# DashDial.net
KiCad netlist of a schematic drawn in EAGLE
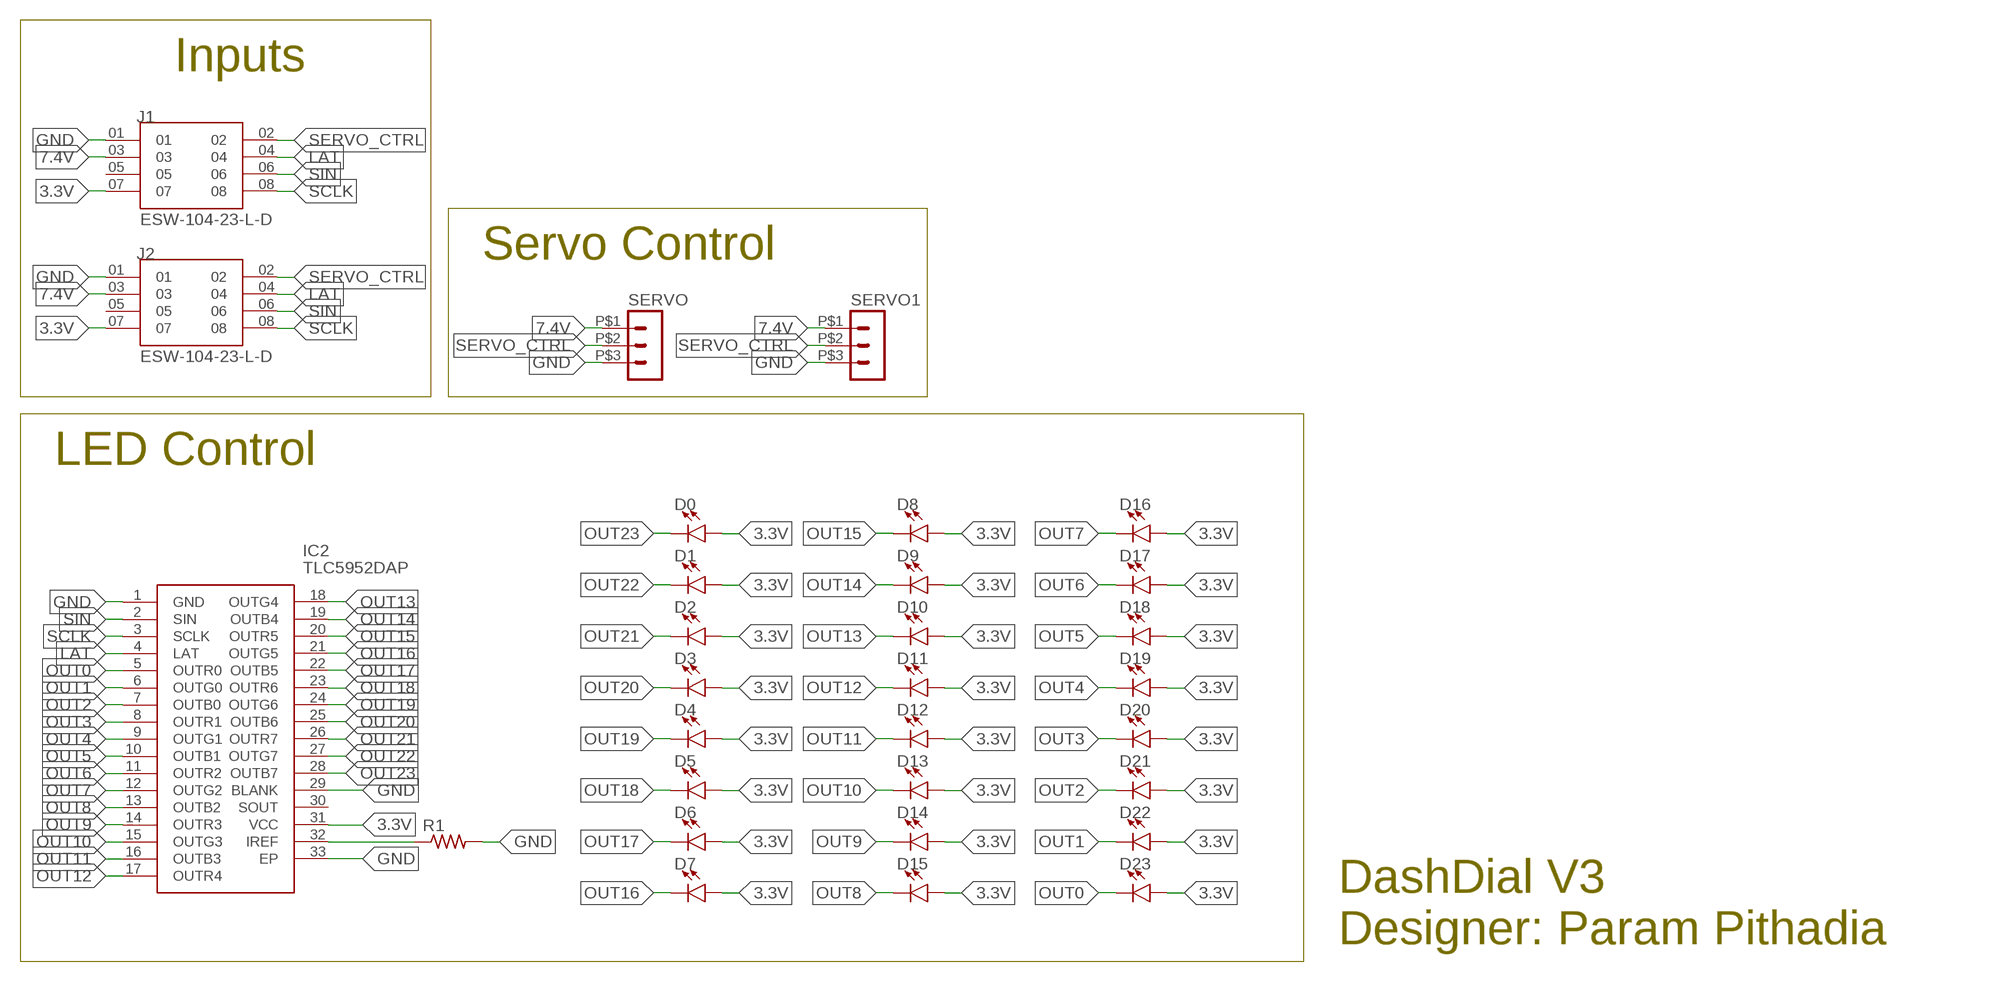
[diagram p0: schematic, sheet 1]

(export (version "E")
  (design (tool "Eeschema 10.0.6"))
  (components
    (comp (ref "D0")
      (value "LED3MM")
      (footprint "eagle-import:LED_3MM")
      (libsource (lib "eagle-import") (part "LED3MM"))
    )
    (comp (ref "D1")
      (value "LED3MM")
      (footprint "eagle-import:LED_3MM")
      (libsource (lib "eagle-import") (part "LED3MM"))
    )
    (comp (ref "D2")
      (value "LED3MM")
      (footprint "eagle-import:LED_3MM")
      (libsource (lib "eagle-import") (part "LED3MM"))
    )
    (comp (ref "D3")
      (value "LED3MM")
      (footprint "eagle-import:LED_3MM")
      (libsource (lib "eagle-import") (part "LED3MM"))
    )
    (comp (ref "D4")
      (value "LED3MM")
      (footprint "eagle-import:LED_3MM")
      (libsource (lib "eagle-import") (part "LED3MM"))
    )
    (comp (ref "D5")
      (value "LED3MM")
      (footprint "eagle-import:LED_3MM")
      (libsource (lib "eagle-import") (part "LED3MM"))
    )
    (comp (ref "D6")
      (value "LED3MM")
      (footprint "eagle-import:LED_3MM")
      (libsource (lib "eagle-import") (part "LED3MM"))
    )
    (comp (ref "D7")
      (value "LED3MM")
      (footprint "eagle-import:LED_3MM")
      (libsource (lib "eagle-import") (part "LED3MM"))
    )
    (comp (ref "D8")
      (value "LED3MM")
      (footprint "eagle-import:LED_3MM")
      (libsource (lib "eagle-import") (part "LED3MM"))
    )
    (comp (ref "D9")
      (value "LED3MM")
      (footprint "eagle-import:LED_3MM")
      (libsource (lib "eagle-import") (part "LED3MM"))
    )
    (comp (ref "D10")
      (value "LED3MM")
      (footprint "eagle-import:LED_3MM")
      (libsource (lib "eagle-import") (part "LED3MM"))
    )
    (comp (ref "D11")
      (value "LED3MM")
      (footprint "eagle-import:LED_3MM")
      (libsource (lib "eagle-import") (part "LED3MM"))
    )
    (comp (ref "D12")
      (value "LED3MM")
      (footprint "eagle-import:LED_3MM")
      (libsource (lib "eagle-import") (part "LED3MM"))
    )
    (comp (ref "D13")
      (value "LED3MM")
      (footprint "eagle-import:LED_3MM")
      (libsource (lib "eagle-import") (part "LED3MM"))
    )
    (comp (ref "D14")
      (value "LED3MM")
      (footprint "eagle-import:LED_3MM")
      (libsource (lib "eagle-import") (part "LED3MM"))
    )
    (comp (ref "D15")
      (value "LED3MM")
      (footprint "eagle-import:LED_3MM")
      (libsource (lib "eagle-import") (part "LED3MM"))
    )
    (comp (ref "D16")
      (value "LED3MM")
      (footprint "eagle-import:LED_3MM")
      (libsource (lib "eagle-import") (part "LED3MM"))
    )
    (comp (ref "D17")
      (value "LED3MM")
      (footprint "eagle-import:LED_3MM")
      (libsource (lib "eagle-import") (part "LED3MM"))
    )
    (comp (ref "D18")
      (value "LED3MM")
      (footprint "eagle-import:LED_3MM")
      (libsource (lib "eagle-import") (part "LED3MM"))
    )
    (comp (ref "D19")
      (value "LED3MM")
      (footprint "eagle-import:LED_3MM")
      (libsource (lib "eagle-import") (part "LED3MM"))
    )
    (comp (ref "D20")
      (value "LED3MM")
      (footprint "eagle-import:LED_3MM")
      (libsource (lib "eagle-import") (part "LED3MM"))
    )
    (comp (ref "D21")
      (value "LED3MM")
      (footprint "eagle-import:LED_3MM")
      (libsource (lib "eagle-import") (part "LED3MM"))
    )
    (comp (ref "D22")
      (value "LED3MM")
      (footprint "eagle-import:LED_3MM")
      (libsource (lib "eagle-import") (part "LED3MM"))
    )
    (comp (ref "D23")
      (value "LED3MM")
      (footprint "eagle-import:LED_3MM")
      (libsource (lib "eagle-import") (part "LED3MM"))
    )
    (comp (ref "IC2")
      (value "TLC5952DAP")
      (footprint "eagle-import:SOP65P810X120-33N")
      (fields (field (name "MOUSER_PART_NUMBER") "595-TLC5952DAP"))
      (libsource (lib "eagle-import") (part "TLC5952DAP"))
    )
    (comp (ref "J1")
      (value "ESW-104-23-L-D")
      (footprint "eagle-import:SAMTEC_ESW-104-23-L-D")
      (fields (field (name "MANUFACTURER") "Samtec Inc."))
      (libsource (lib "eagle-import") (part "ESW-104-23-L-D"))
    )
    (comp (ref "J2")
      (value "ESW-104-23-L-D")
      (footprint "eagle-import:SAMTEC_ESW-104-23-L-D")
      (fields (field (name "MANUFACTURER") "Samtec Inc."))
      (libsource (lib "eagle-import") (part "ESW-104-23-L-D"))
    )
    (comp (ref "R1")
      (value "RES_SMDR0603")
      (footprint "eagle-import:R0603")
      (libsource (lib "eagle-import") (part "RES_SMDR0603"))
    )
    (comp (ref "SERVO")
      (value "HEADER_POS3_43650-0300")
      (footprint "eagle-import:43650-0300")
      (libsource (lib "eagle-import") (part "HEADER_POS3_?43650-0300"))
    )
    (comp (ref "SERVO1")
      (value "HEADER_POS3_43650-0300")
      (footprint "eagle-import:43650-0300")
      (libsource (lib "eagle-import") (part "HEADER_POS3_?43650-0300"))
    )
  )
  (nets
    (net (code "1") (name "3.3V") (class "Default")
      (node (ref "D0") (pin "A") (pinfunction "A_A") (pintype "passive"))
      (node (ref "D1") (pin "A") (pinfunction "A_A") (pintype "passive"))
      (node (ref "D10") (pin "A") (pinfunction "A_A") (pintype "passive"))
      (node (ref "D11") (pin "A") (pinfunction "A_A") (pintype "passive"))
      (node (ref "D12") (pin "A") (pinfunction "A_A") (pintype "passive"))
      (node (ref "D13") (pin "A") (pinfunction "A_A") (pintype "passive"))
      (node (ref "D14") (pin "A") (pinfunction "A_A") (pintype "passive"))
      (node (ref "D15") (pin "A") (pinfunction "A_A") (pintype "passive"))
      (node (ref "D16") (pin "A") (pinfunction "A_A") (pintype "passive"))
      (node (ref "D17") (pin "A") (pinfunction "A_A") (pintype "passive"))
      (node (ref "D18") (pin "A") (pinfunction "A_A") (pintype "passive"))
      (node (ref "D19") (pin "A") (pinfunction "A_A") (pintype "passive"))
      (node (ref "D2") (pin "A") (pinfunction "A_A") (pintype "passive"))
      (node (ref "D20") (pin "A") (pinfunction "A_A") (pintype "passive"))
      (node (ref "D21") (pin "A") (pinfunction "A_A") (pintype "passive"))
      (node (ref "D22") (pin "A") (pinfunction "A_A") (pintype "passive"))
      (node (ref "D23") (pin "A") (pinfunction "A_A") (pintype "passive"))
      (node (ref "D3") (pin "A") (pinfunction "A_A") (pintype "passive"))
      (node (ref "D4") (pin "A") (pinfunction "A_A") (pintype "passive"))
      (node (ref "D5") (pin "A") (pinfunction "A_A") (pintype "passive"))
      (node (ref "D6") (pin "A") (pinfunction "A_A") (pintype "passive"))
      (node (ref "D7") (pin "A") (pinfunction "A_A") (pintype "passive"))
      (node (ref "D8") (pin "A") (pinfunction "A_A") (pintype "passive"))
      (node (ref "D9") (pin "A") (pinfunction "A_A") (pintype "passive"))
      (node (ref "IC2") (pin "31") (pinfunction "VCC_31") (pintype "bidirectional"))
      (node (ref "J1") (pin "07") (pinfunction "07_07") (pintype "passive"))
      (node (ref "J2") (pin "07") (pinfunction "07_07") (pintype "passive"))
    )
    (net (code "2") (name "7.4V") (class "Default")
      (node (ref "J1") (pin "03") (pinfunction "03_03") (pintype "passive"))
      (node (ref "J2") (pin "03") (pinfunction "03_03") (pintype "passive"))
      (node (ref "SERVO") (pin "P$1") (pinfunction "1_P$1") (pintype "passive"))
      (node (ref "SERVO1") (pin "P$1") (pinfunction "1_P$1") (pintype "passive"))
    )
    (net (code "3") (name "GND") (class "Default")
      (node (ref "IC2") (pin "1") (pinfunction "GND_1") (pintype "bidirectional"))
      (node (ref "IC2") (pin "29") (pinfunction "BLANK_29") (pintype "bidirectional"))
      (node (ref "IC2") (pin "33") (pinfunction "EP_33") (pintype "bidirectional"))
      (node (ref "J1") (pin "01") (pinfunction "01_01") (pintype "passive"))
      (node (ref "J2") (pin "01") (pinfunction "01_01") (pintype "passive"))
      (node (ref "R1") (pin "2") (pinfunction "2_2") (pintype "passive"))
      (node (ref "SERVO") (pin "P$3") (pinfunction "3_P$3") (pintype "passive"))
      (node (ref "SERVO1") (pin "P$3") (pinfunction "3_P$3") (pintype "passive"))
    )
    (net (code "4") (name "LAT") (class "Default")
      (node (ref "IC2") (pin "4") (pinfunction "LAT_4") (pintype "bidirectional"))
      (node (ref "J1") (pin "04") (pinfunction "04_04") (pintype "passive"))
      (node (ref "J2") (pin "04") (pinfunction "04_04") (pintype "passive"))
    )
    (net (code "5") (name "Net-(IC2-IREF)") (class "Default")
      (node (ref "IC2") (pin "32") (pinfunction "IREF_32") (pintype "bidirectional"))
      (node (ref "R1") (pin "1") (pinfunction "1_1") (pintype "passive"))
    )
    (net (code "6") (name "OUT0") (class "Default")
      (node (ref "D23") (pin "K") (pinfunction "C_K") (pintype "passive"))
      (node (ref "IC2") (pin "5") (pinfunction "OUTR0_5") (pintype "bidirectional"))
    )
    (net (code "7") (name "OUT1") (class "Default")
      (node (ref "D22") (pin "K") (pinfunction "C_K") (pintype "passive"))
      (node (ref "IC2") (pin "6") (pinfunction "OUTG0_6") (pintype "bidirectional"))
    )
    (net (code "8") (name "OUT2") (class "Default")
      (node (ref "D21") (pin "K") (pinfunction "C_K") (pintype "passive"))
      (node (ref "IC2") (pin "7") (pinfunction "OUTB0_7") (pintype "bidirectional"))
    )
    (net (code "9") (name "OUT3") (class "Default")
      (node (ref "D20") (pin "K") (pinfunction "C_K") (pintype "passive"))
      (node (ref "IC2") (pin "8") (pinfunction "OUTR1_8") (pintype "bidirectional"))
    )
    (net (code "10") (name "OUT4") (class "Default")
      (node (ref "D19") (pin "K") (pinfunction "C_K") (pintype "passive"))
      (node (ref "IC2") (pin "9") (pinfunction "OUTG1_9") (pintype "bidirectional"))
    )
    (net (code "11") (name "OUT5") (class "Default")
      (node (ref "D18") (pin "K") (pinfunction "C_K") (pintype "passive"))
      (node (ref "IC2") (pin "10") (pinfunction "OUTB1_10") (pintype "bidirectional"))
    )
    (net (code "12") (name "OUT6") (class "Default")
      (node (ref "D17") (pin "K") (pinfunction "C_K") (pintype "passive"))
      (node (ref "IC2") (pin "11") (pinfunction "OUTR2_11") (pintype "bidirectional"))
    )
    (net (code "13") (name "OUT7") (class "Default")
      (node (ref "D16") (pin "K") (pinfunction "C_K") (pintype "passive"))
      (node (ref "IC2") (pin "12") (pinfunction "OUTG2_12") (pintype "bidirectional"))
    )
    (net (code "14") (name "OUT8") (class "Default")
      (node (ref "D15") (pin "K") (pinfunction "C_K") (pintype "passive"))
      (node (ref "IC2") (pin "13") (pinfunction "OUTB2_13") (pintype "bidirectional"))
    )
    (net (code "15") (name "OUT9") (class "Default")
      (node (ref "D14") (pin "K") (pinfunction "C_K") (pintype "passive"))
      (node (ref "IC2") (pin "14") (pinfunction "OUTR3_14") (pintype "bidirectional"))
    )
    (net (code "16") (name "OUT10") (class "Default")
      (node (ref "D13") (pin "K") (pinfunction "C_K") (pintype "passive"))
      (node (ref "IC2") (pin "15") (pinfunction "OUTG3_15") (pintype "bidirectional"))
    )
    (net (code "17") (name "OUT11") (class "Default")
      (node (ref "D12") (pin "K") (pinfunction "C_K") (pintype "passive"))
      (node (ref "IC2") (pin "16") (pinfunction "OUTB3_16") (pintype "bidirectional"))
    )
    (net (code "18") (name "OUT12") (class "Default")
      (node (ref "D11") (pin "K") (pinfunction "C_K") (pintype "passive"))
      (node (ref "IC2") (pin "17") (pinfunction "OUTR4_17") (pintype "bidirectional"))
    )
    (net (code "19") (name "OUT13") (class "Default")
      (node (ref "D10") (pin "K") (pinfunction "C_K") (pintype "passive"))
      (node (ref "IC2") (pin "18") (pinfunction "OUTG4_18") (pintype "bidirectional"))
    )
    (net (code "20") (name "OUT14") (class "Default")
      (node (ref "D9") (pin "K") (pinfunction "C_K") (pintype "passive"))
      (node (ref "IC2") (pin "19") (pinfunction "OUTB4_19") (pintype "bidirectional"))
    )
    (net (code "21") (name "OUT15") (class "Default")
      (node (ref "D8") (pin "K") (pinfunction "C_K") (pintype "passive"))
      (node (ref "IC2") (pin "20") (pinfunction "OUTR5_20") (pintype "bidirectional"))
    )
    (net (code "22") (name "OUT16") (class "Default")
      (node (ref "D7") (pin "K") (pinfunction "C_K") (pintype "passive"))
      (node (ref "IC2") (pin "21") (pinfunction "OUTG5_21") (pintype "bidirectional"))
    )
    (net (code "23") (name "OUT17") (class "Default")
      (node (ref "D6") (pin "K") (pinfunction "C_K") (pintype "passive"))
      (node (ref "IC2") (pin "22") (pinfunction "OUTB5_22") (pintype "bidirectional"))
    )
    (net (code "24") (name "OUT18") (class "Default")
      (node (ref "D5") (pin "K") (pinfunction "C_K") (pintype "passive"))
      (node (ref "IC2") (pin "23") (pinfunction "OUTR6_23") (pintype "bidirectional"))
    )
    (net (code "25") (name "OUT19") (class "Default")
      (node (ref "D4") (pin "K") (pinfunction "C_K") (pintype "passive"))
      (node (ref "IC2") (pin "24") (pinfunction "OUTG6_24") (pintype "bidirectional"))
    )
    (net (code "26") (name "OUT20") (class "Default")
      (node (ref "D3") (pin "K") (pinfunction "C_K") (pintype "passive"))
      (node (ref "IC2") (pin "25") (pinfunction "OUTB6_25") (pintype "bidirectional"))
    )
    (net (code "27") (name "OUT21") (class "Default")
      (node (ref "D2") (pin "K") (pinfunction "C_K") (pintype "passive"))
      (node (ref "IC2") (pin "26") (pinfunction "OUTR7_26") (pintype "bidirectional"))
    )
    (net (code "28") (name "OUT22") (class "Default")
      (node (ref "D1") (pin "K") (pinfunction "C_K") (pintype "passive"))
      (node (ref "IC2") (pin "27") (pinfunction "OUTG7_27") (pintype "bidirectional"))
    )
    (net (code "29") (name "OUT23") (class "Default")
      (node (ref "D0") (pin "K") (pinfunction "C_K") (pintype "passive"))
      (node (ref "IC2") (pin "28") (pinfunction "OUTB7_28") (pintype "bidirectional"))
    )
    (net (code "30") (name "SCLK") (class "Default")
      (node (ref "IC2") (pin "3") (pinfunction "SCLK_3") (pintype "bidirectional"))
      (node (ref "J1") (pin "08") (pinfunction "08_08") (pintype "passive"))
      (node (ref "J2") (pin "08") (pinfunction "08_08") (pintype "passive"))
    )
    (net (code "31") (name "SERVO_CTRL") (class "Default")
      (node (ref "J1") (pin "02") (pinfunction "02_02") (pintype "passive"))
      (node (ref "J2") (pin "02") (pinfunction "02_02") (pintype "passive"))
      (node (ref "SERVO") (pin "P$2") (pinfunction "2_P$2") (pintype "passive"))
      (node (ref "SERVO1") (pin "P$2") (pinfunction "2_P$2") (pintype "passive"))
    )
    (net (code "32") (name "SIN") (class "Default")
      (node (ref "IC2") (pin "2") (pinfunction "SIN_2") (pintype "bidirectional"))
      (node (ref "J1") (pin "06") (pinfunction "06_06") (pintype "passive"))
      (node (ref "J2") (pin "06") (pinfunction "06_06") (pintype "passive"))
    )
    (net (code "33") (name "unconnected-(IC2-SOUT-Pad30)") (class "Default")
      (node (ref "IC2") (pin "30") (pinfunction "SOUT_30") (pintype "bidirectional"))
    )
    (net (code "34") (name "unconnected-(J1-Pad05)") (class "Default")
      (node (ref "J1") (pin "05") (pinfunction "05_05") (pintype "passive"))
    )
    (net (code "35") (name "unconnected-(J2-Pad05)") (class "Default")
      (node (ref "J2") (pin "05") (pinfunction "05_05") (pintype "passive"))
    )
  )
)
